# Accesoire_antenne_et_buzzer.net
KiCad netlist of a schematic drawn in Altium Designer
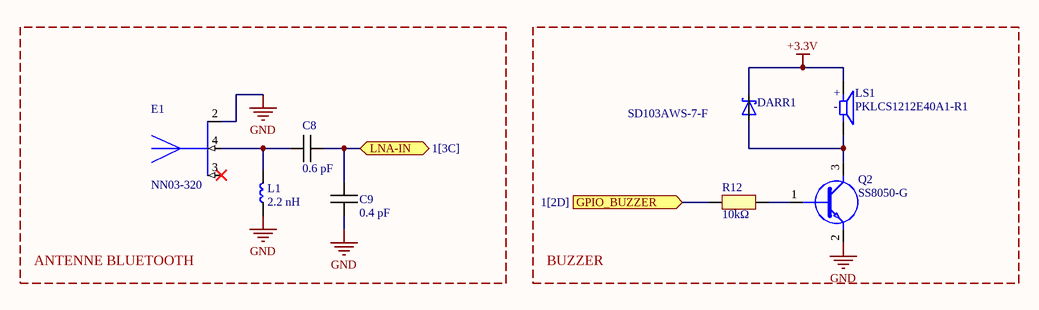
[diagram p0: Accesoire antenne et buzzer.SchDoc]

(export (version "E")
  (design (tool "Eeschema 10.0.6"))
  (components
    (comp (ref "C8")
      (value "0.6 pF")
      (footprint "CAPC1005X06N")
      (libsource (lib "SCHLibrary") (part "Capacitor"))
    )
    (comp (ref "C9")
      (value "0.4 pF")
      (footprint "CAPC1005X06N")
      (libsource (lib "SCHLibrary") (part "Capacitor"))
    )
    (comp (ref "DARR1")
      (value "SD103AWS-7-F")
      (footprint "SD103AWS-7-F")
      (description "Diode Array 3 Independent Schottky 40V 175mA Surface Mount 6-TSSOP, SC-88, SOT-363")
      (libsource (lib "SCHLibrary") (part "SD103AWS-7-F"))
    )
    (comp (ref "E1")
      (value "NN03-320")
      (footprint "XCVR_NN03-320")
      (fields (field (name "MOUSER PART NUMBER") "128-NN03-320"))
      (libsource (lib "SCHLibrary") (part "NN03-320"))
    )
    (comp (ref "L1")
      (value "2.2 nH")
      (footprint "LQPC1005X06N")
      (libsource (lib "SCHLibrary") (part "Bobine"))
    )
    (comp (ref "LS1")
      (value "PKLCS1212E40A1-R1")
      (footprint "PCBLibrary:SPKR_PKLCS1212E40A1-R1")
      (description "Buzzers Transducer, Externally Driven Piezo 1.5V 2kHz 70dB @ 1.5V, 10cm Surface Mount Solder Pads")
      (fields (field (name "MF") "Murata Electronics"))
      (libsource (lib "SCHLibrary") (part "PKLCS1212E40A1-R1"))
    )
    (comp (ref "Q2")
      (value "SS8050-G")
      (footprint "SS8050-G")
      (description "Bipolar Transistors - BJT NPN TRANSISTOR 1.5A 40V")
      (libsource (lib "SCHLibrary") (part "SS8050-G"))
    )
    (comp (ref "R12")
      (value "10kΩ")
      (footprint "RESC1005X06N")
      (libsource (lib "SCHLibrary") (part "Resistor"))
    )
  )
  (nets
    (net (code "1") (name "+3.3V") (class "Default")
      (node (ref "DARR1") (pin "1") (pinfunction "C_1") (pintype "passive"))
      (node (ref "LS1") (pin "P") (pinfunction "P_P") (pintype "passive"))
    )
    (net (code "2") (name "/GPIO_BUZZER") (class "Default")
      (node (ref "R12") (pin "1") (pinfunction "1_1") (pintype "passive"))
    )
    (net (code "3") (name "/LNA-IN") (class "Default")
      (node (ref "C8") (pin "1") (pinfunction "1_1") (pintype "passive"))
      (node (ref "C9") (pin "1") (pinfunction "1_1") (pintype "passive"))
    )
    (net (code "4") (name "GND") (class "Default")
      (node (ref "C9") (pin "2") (pinfunction "2_2") (pintype "passive"))
      (node (ref "E1") (pin "2") (pinfunction "GROUND_2") (pintype "power_in"))
      (node (ref "L1") (pin "1") (pinfunction "1_1") (pintype "passive"))
      (node (ref "Q2") (pin "2") (pinfunction "E_2") (pintype "passive"))
    )
    (net (code "5") (name "Net-(DARR1-A)") (class "Default")
      (node (ref "DARR1") (pin "2") (pinfunction "A_2") (pintype "passive"))
      (node (ref "LS1") (pin "N") (pinfunction "N_N") (pintype "passive"))
      (node (ref "Q2") (pin "3") (pinfunction "C_3") (pintype "passive"))
    )
    (net (code "6") (name "Net-(E1-FEED_GNSS)") (class "Default")
      (node (ref "C8") (pin "2") (pinfunction "2_2") (pintype "passive"))
      (node (ref "E1") (pin "4") (pinfunction "FEED_GNSS_4") (pintype "input"))
      (node (ref "L1") (pin "2") (pinfunction "2_2") (pintype "passive"))
    )
    (net (code "7") (name "Net-(Q2-B)") (class "Default")
      (node (ref "Q2") (pin "1") (pinfunction "B_1") (pintype "passive"))
      (node (ref "R12") (pin "2") (pinfunction "2_2") (pintype "passive"))
    )
    (net (code "8") (name "unconnected-(E1-FEED_BLUETOOTH-Pad3)") (class "Default")
      (node (ref "E1") (pin "3") (pinfunction "FEED_BLUETOOTH_3") (pintype "input+no_connect"))
    )
  )
)
